# Sheet1.net
KiCad netlist of a schematic drawn in Altium Designer
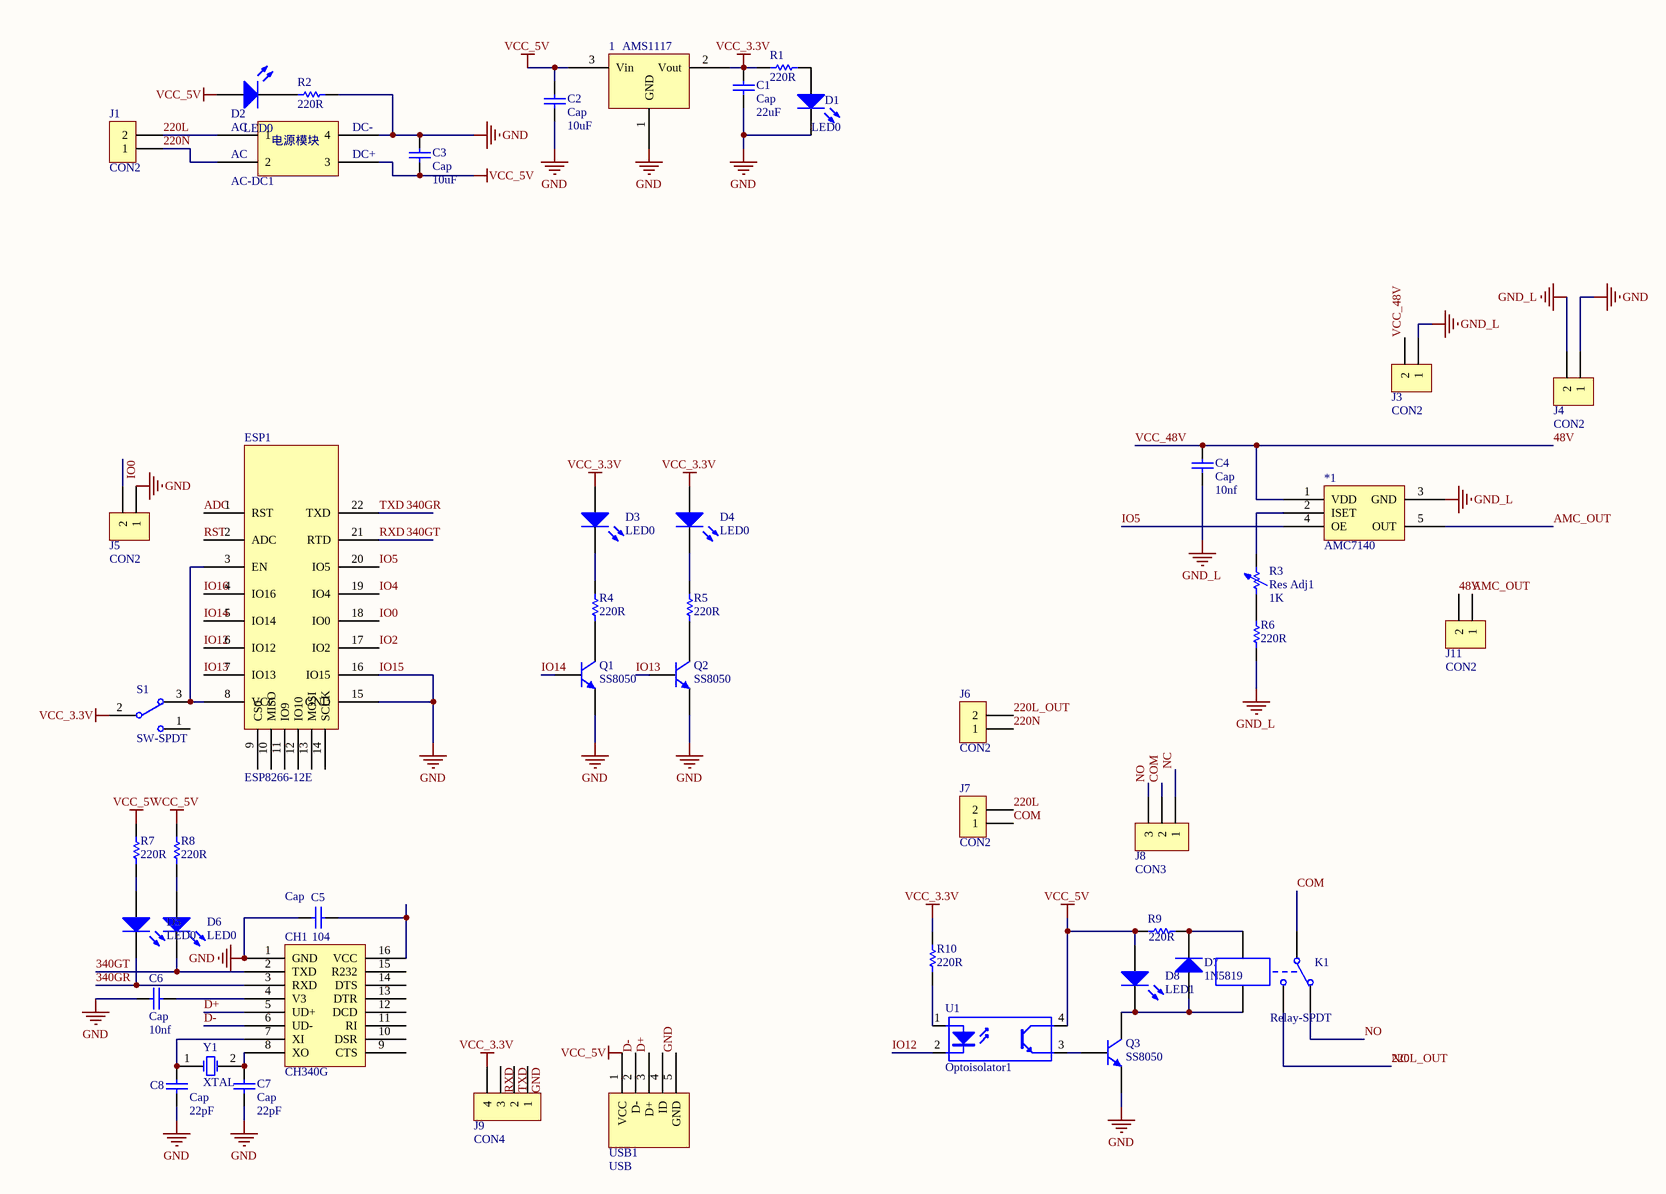
[diagram p0: Sheet1.SchDoc]

(export (version "E")
  (design (tool "Eeschema 10.0.6"))
  (components
    (comp (ref "*1") (value "AMC7140") (footprint "TO-252-5L") (libsource (lib "传感器") (part "AMC7140")))
    (comp (ref "1") (value "AMS1117") (footprint "SOT223") (libsource (lib "开关电路") (part "AMS1117")))
    (comp (ref "AC-DC1") (value "220—5") (footprint "POWER-220_5") (libsource (lib "开关电路") (part "220—5")))
    (comp (ref "C1")
      (value "Cap")
      (footprint "1206")
      (description "Capacitor")
      (fields (field (name "ALTIUM_VALUE") "22uF") (field (name "PUBLISHER") "Altium Limited"))
      (libsource (lib "Miscellaneous Devices0") (part "Cap"))
    )
    (comp (ref "C2")
      (value "Cap")
      (footprint "1206")
      (description "Capacitor")
      (fields (field (name "ALTIUM_VALUE") "10uF") (field (name "PUBLISHER") "Altium Limited"))
      (libsource (lib "Miscellaneous Devices0") (part "Cap"))
    )
    (comp (ref "C3")
      (value "Cap")
      (footprint "CAP-E SMD 8X8")
      (description "Capacitor")
      (fields (field (name "ALTIUM_VALUE") "10uF") (field (name "PUBLISHER") "Altium Limited"))
      (libsource (lib "Miscellaneous Devices0") (part "Cap"))
    )
    (comp (ref "C4")
      (value "Cap")
      (footprint "0805")
      (description "Capacitor")
      (fields (field (name "ALTIUM_VALUE") "10nf") (field (name "PUBLISHER") "Altium Limited"))
      (libsource (lib "Miscellaneous Devices0") (part "Cap"))
    )
    (comp (ref "C5")
      (value "Cap")
      (footprint "0805")
      (description "Capacitor")
      (fields (field (name "ALTIUM_VALUE") "104") (field (name "PUBLISHER") "Altium Limited"))
      (libsource (lib "Miscellaneous Devices0") (part "Cap"))
    )
    (comp (ref "C6")
      (value "Cap")
      (footprint "0805")
      (description "Capacitor")
      (fields (field (name "ALTIUM_VALUE") "10nf") (field (name "PUBLISHER") "Altium Limited"))
      (libsource (lib "Miscellaneous Devices0") (part "Cap"))
    )
    (comp (ref "C7")
      (value "Cap")
      (footprint "0805")
      (description "Capacitor")
      (fields (field (name "ALTIUM_VALUE") "22pF") (field (name "PUBLISHER") "Altium Limited"))
      (libsource (lib "Miscellaneous Devices0") (part "Cap"))
    )
    (comp (ref "C8")
      (value "Cap")
      (footprint "0805")
      (description "Capacitor")
      (fields (field (name "ALTIUM_VALUE") "22pF") (field (name "PUBLISHER") "Altium Limited"))
      (libsource (lib "Miscellaneous Devices0") (part "Cap"))
    )
    (comp (ref "CH1") (value "CH340G") (footprint "SO:SOP16") (libsource (lib "CH340") (part "CH340G")))
    (comp (ref "D1")
      (value "LED0")
      (footprint "ZH常用封装ZH:LED0805")
      (description "Typical INFRARED GaAs LED")
      (fields (field (name "PUBLISHER") "Altium Limited"))
      (libsource (lib "Miscellaneous Devices") (part "LED0"))
    )
    (comp (ref "D2")
      (value "LED0")
      (footprint "ZH常用封装ZH:LED0805")
      (description "Typical INFRARED GaAs LED")
      (fields (field (name "PUBLISHER") "Altium Limited"))
      (libsource (lib "Miscellaneous Devices") (part "LED0"))
    )
    (comp (ref "D3")
      (value "LED0")
      (footprint "ZH常用封装ZH:LED0805")
      (description "Typical INFRARED GaAs LED")
      (fields (field (name "PUBLISHER") "Altium Limited"))
      (libsource (lib "Miscellaneous Devices") (part "LED0"))
    )
    (comp (ref "D4")
      (value "LED0")
      (footprint "ZH常用封装ZH:LED0805")
      (description "Typical INFRARED GaAs LED")
      (fields (field (name "PUBLISHER") "Altium Limited"))
      (libsource (lib "Miscellaneous Devices") (part "LED0"))
    )
    (comp (ref "D5")
      (value "LED0")
      (footprint "ZH常用封装ZH:LED0805")
      (description "Typical INFRARED GaAs LED")
      (fields (field (name "PUBLISHER") "Altium Limited"))
      (libsource (lib "Miscellaneous Devices") (part "LED0"))
    )
    (comp (ref "D6")
      (value "LED0")
      (footprint "ZH常用封装ZH:LED0805")
      (description "Typical INFRARED GaAs LED")
      (fields (field (name "PUBLISHER") "Altium Limited"))
      (libsource (lib "Miscellaneous Devices") (part "LED0"))
    )
    (comp (ref "D7")
      (value "1N5819")
      (footprint "ZH常用封装ZH:DO-214AC/SMA")
      (description "Default Diode")
      (fields (field (name "PUBLISHER") "Altium Limited"))
      (libsource (lib "Miscellaneous Devices") (part "Diode"))
    )
    (comp (ref "D8")
      (value "LED1")
      (footprint "ZH常用封装ZH:LED0805")
      (description "Typical RED GaAs LED")
      (fields (field (name "PUBLISHER") "Altium Limited"))
      (libsource (lib "Miscellaneous Devices") (part "LED1"))
    )
    (comp (ref "ESP1")
      (value "ESP8266-12E")
      (footprint "ZH常用封装ZH:ESP8266")
      (libsource (lib "开关电路") (part "ESP8266"))
    )
    (comp (ref "J1")
      (value "CON2")
      (footprint "miniUSB-b:TML-2-5.08")
      (description "Connector")
      (libsource (lib "") (part "CON2_1"))
    )
    (comp (ref "J3")
      (value "CON2")
      (footprint "miniUSB-b:TML-2-5.08")
      (description "Connector")
      (libsource (lib "插件") (part "CON2"))
    )
    (comp (ref "J4")
      (value "CON2")
      (footprint "HDR1X2")
      (description "Connector")
      (libsource (lib "插件") (part "CON2"))
    )
    (comp (ref "J5")
      (value "CON2")
      (footprint "HDR1X2")
      (description "Connector")
      (libsource (lib "插件") (part "CON2"))
    )
    (comp (ref "J6")
      (value "CON2")
      (footprint "miniUSB-b:TML-2-5.08")
      (description "Connector")
      (libsource (lib "") (part "CON2_1"))
    )
    (comp (ref "J7")
      (value "CON2")
      (footprint "HDR1X2")
      (description "Connector")
      (libsource (lib "") (part "CON2_1"))
    )
    (comp (ref "J8")
      (value "CON3")
      (footprint "TML-3-5.08")
      (description "Connector")
      (libsource (lib "插件") (part "CON3"))
    )
    (comp (ref "J9")
      (value "CON4")
      (footprint "SIP4")
      (description "Connector")
      (libsource (lib "开关电路") (part "CON4"))
    )
    (comp (ref "J11")
      (value "CON2")
      (footprint "miniUSB-b:TML-2-5.08")
      (description "Connector")
      (libsource (lib "插件") (part "CON2"))
    )
    (comp (ref "K1")
      (value "Relay-SPDT")
      (footprint "5V-5")
      (description "Single-Pole Dual-Throw Relay")
      (fields (field (name "PUBLISHER") "Altium Limited"))
      (libsource (lib "Miscellaneous Devices") (part "Relay-SPDT"))
    )
    (comp (ref "Q1")
      (value "SS8050")
      (footprint "SOT-23")
      (description "NPN General Purpose Amplifier")
      (fields (field (name "PUBLISHER") "Altium Limited"))
      (libsource (lib "Miscellaneous Devices") (part "2N3904"))
    )
    (comp (ref "Q2")
      (value "SS8050")
      (footprint "SOT-23")
      (description "NPN General Purpose Amplifier")
      (fields (field (name "PUBLISHER") "Altium Limited"))
      (libsource (lib "Miscellaneous Devices") (part "2N3904"))
    )
    (comp (ref "Q3")
      (value "SS8050")
      (footprint "SOT-23")
      (description "NPN General Purpose Amplifier")
      (fields (field (name "PUBLISHER") "Altium Limited"))
      (libsource (lib "Miscellaneous Devices") (part "2N3904"))
    )
    (comp (ref "R1")
      (value "220R")
      (footprint "贴片:0805")
      (description "Resistor")
      (fields (field (name "Comment") "Res") (field (name "PUBLISHER") "Altium Limited"))
      (libsource (lib "电阻电容") (part "Res"))
    )
    (comp (ref "R2")
      (value "220R")
      (footprint "贴片:0805")
      (description "Resistor")
      (fields (field (name "Comment") "Res") (field (name "PUBLISHER") "Altium Limited"))
      (libsource (lib "电阻电容") (part "Res"))
    )
    (comp (ref "R3")
      (value "Res Adj1")
      (footprint "RES ADJ-3296W")
      (description "Variable Resistor")
      (fields (field (name "ALTIUM_VALUE") "1K") (field (name "PUBLISHER") "Altium Limited"))
      (libsource (lib "Miscellaneous Devices") (part "Res Adj1"))
    )
    (comp (ref "R4")
      (value "220R")
      (footprint "贴片:0805")
      (description "Resistor")
      (fields (field (name "Comment") "Res") (field (name "PUBLISHER") "Altium Limited"))
      (libsource (lib "电阻电容") (part "Res"))
    )
    (comp (ref "R5")
      (value "220R")
      (footprint "贴片:0805")
      (description "Resistor")
      (fields (field (name "Comment") "Res") (field (name "PUBLISHER") "Altium Limited"))
      (libsource (lib "电阻电容") (part "Res"))
    )
    (comp (ref "R6")
      (value "220R")
      (footprint "贴片:0805")
      (description "Resistor")
      (fields (field (name "Comment") "Res") (field (name "PUBLISHER") "Altium Limited"))
      (libsource (lib "电阻电容") (part "Res"))
    )
    (comp (ref "R7")
      (value "220R")
      (footprint "贴片:0805")
      (description "Resistor")
      (fields (field (name "Comment") "Res") (field (name "PUBLISHER") "Altium Limited"))
      (libsource (lib "电阻电容") (part "Res"))
    )
    (comp (ref "R8")
      (value "220R")
      (footprint "贴片:0805")
      (description "Resistor")
      (fields (field (name "Comment") "Res") (field (name "PUBLISHER") "Altium Limited"))
      (libsource (lib "电阻电容") (part "Res"))
    )
    (comp (ref "R9")
      (value "220R")
      (footprint "贴片:0805")
      (description "Resistor")
      (fields (field (name "Comment") "Res") (field (name "PUBLISHER") "Altium Limited"))
      (libsource (lib "电阻电容") (part "Res"))
    )
    (comp (ref "R10")
      (value "220R")
      (footprint "贴片:0805")
      (description "Resistor")
      (fields (field (name "Comment") "Res") (field (name "PUBLISHER") "Altium Limited"))
      (libsource (lib "电阻电容") (part "Res"))
    )
    (comp (ref "S1")
      (value "SW-SPDT")
      (footprint "SS12D00G3")
      (description "SPDT Subminiature Toggle Switch, Right Angle Mounting, Vertical Actuation")
      (fields (field (name "PUBLISHER") "Altium Limited"))
      (libsource (lib "Miscellaneous Devices") (part "SW-SPDT"))
    )
    (comp (ref "U1")
      (value "Optoisolator1")
      (footprint "DIP4")
      (description "4-Pin Phototransistor Optocoupler")
      (fields (field (name "PUBLISHER") "Altium Limited"))
      (libsource (lib "Miscellaneous Devices") (part "Optoisolator1"))
    )
    (comp (ref "USB1")
      (value "USB")
      (footprint "ZH常用封装ZH:USB-MINI")
      (libsource (lib "CH340") (part "miniUSB-b"))
    )
    (comp (ref "Y1")
      (value "XTAL")
      (footprint "XTAL")
      (description "Crystal Oscillator")
      (fields (field (name "PUBLISHER") "Altium Limited"))
      (libsource (lib "Miscellaneous Devices0") (part "XTAL"))
    )
  )
  (nets
    (net (code "1") (name "/48V") (class "Default")
      (node (ref "*1") (pin "1") (pinfunction "VDD_1") (pintype "passive"))
      (node (ref "C4") (pin "1") (pinfunction "1_1") (pintype "passive"))
      (node (ref "J11") (pin "2") (pinfunction "2_2") (pintype "passive"))
      (node (ref "J3") (pin "2") (pinfunction "2_2") (pintype "passive"))
    )
    (net (code "2") (name "/220L") (class "Default")
      (node (ref "AC-DC1") (pin "1") (pinfunction "1_1") (pintype "passive"))
      (node (ref "J1") (pin "2") (pinfunction "2_2") (pintype "passive"))
      (node (ref "J7") (pin "2") (pinfunction "2_2") (pintype "passive"))
    )
    (net (code "3") (name "/220L_OUT") (class "Default")
      (node (ref "J6") (pin "2") (pinfunction "2_2") (pintype "passive"))
      (node (ref "J8") (pin "1") (pinfunction "1_1") (pintype "passive"))
      (node (ref "K1") (pin "3") (pinfunction "3_3") (pintype "passive"))
    )
    (net (code "4") (name "/220N") (class "Default")
      (node (ref "AC-DC1") (pin "2") (pinfunction "2_2") (pintype "passive"))
      (node (ref "J1") (pin "1") (pinfunction "1_1") (pintype "passive"))
      (node (ref "J6") (pin "1") (pinfunction "1_1") (pintype "passive"))
    )
    (net (code "5") (name "/340GR") (class "Default")
      (node (ref "CH1") (pin "3") (pinfunction "RXD_3") (pintype "passive"))
      (node (ref "D5") (pin "2") (pinfunction "K_2") (pintype "passive"))
      (node (ref "ESP1") (pin "22") (pinfunction "TXD_22") (pintype "passive"))
      (node (ref "J9") (pin "2") (pinfunction "2_2") (pintype "passive"))
    )
    (net (code "6") (name "/340GT") (class "Default")
      (node (ref "CH1") (pin "2") (pinfunction "TXD_2") (pintype "passive"))
      (node (ref "D6") (pin "2") (pinfunction "K_2") (pintype "passive"))
      (node (ref "ESP1") (pin "21") (pinfunction "RTD_21") (pintype "passive"))
      (node (ref "J9") (pin "3") (pinfunction "3_3") (pintype "passive"))
    )
    (net (code "7") (name "/ADC") (class "Default")
      (node (ref "ESP1") (pin "1") (pinfunction "RST_1") (pintype "passive"))
    )
    (net (code "8") (name "/AMC_OUT") (class "Default")
      (node (ref "*1") (pin "5") (pinfunction "OUT_5") (pintype "passive"))
      (node (ref "J11") (pin "1") (pinfunction "1_1") (pintype "passive"))
    )
    (net (code "9") (name "/COM") (class "Default")
      (node (ref "J7") (pin "1") (pinfunction "1_1") (pintype "passive"))
      (node (ref "J8") (pin "2") (pinfunction "2_2") (pintype "passive"))
      (node (ref "K1") (pin "1") (pinfunction "1_1") (pintype "passive"))
    )
    (net (code "10") (name "/D+") (class "Default")
      (node (ref "CH1") (pin "5") (pinfunction "UD+_5") (pintype "passive"))
      (node (ref "USB1") (pin "3") (pinfunction "D+_3") (pintype "passive"))
    )
    (net (code "11") (name "/D-") (class "Default")
      (node (ref "CH1") (pin "6") (pinfunction "UD-_6") (pintype "passive"))
      (node (ref "USB1") (pin "2") (pinfunction "D-_2") (pintype "passive"))
    )
    (net (code "12") (name "/IO0") (class "Default")
      (node (ref "ESP1") (pin "18") (pinfunction "IO0_18") (pintype "passive"))
      (node (ref "J5") (pin "2") (pinfunction "2_2") (pintype "passive"))
    )
    (net (code "13") (name "/IO2") (class "Default")
      (node (ref "ESP1") (pin "17") (pinfunction "IO2_17") (pintype "passive"))
    )
    (net (code "14") (name "/IO4") (class "Default")
      (node (ref "ESP1") (pin "19") (pinfunction "IO4_19") (pintype "passive"))
    )
    (net (code "15") (name "/IO5") (class "Default")
      (node (ref "*1") (pin "4") (pinfunction "OE_4") (pintype "passive"))
      (node (ref "ESP1") (pin "20") (pinfunction "IO5_20") (pintype "passive"))
    )
    (net (code "16") (name "/IO12") (class "Default")
      (node (ref "ESP1") (pin "6") (pinfunction "IO12_6") (pintype "passive"))
      (node (ref "U1") (pin "2") (pinfunction "K_2") (pintype "passive"))
    )
    (net (code "17") (name "/IO13") (class "Default")
      (node (ref "ESP1") (pin "7") (pinfunction "IO13_7") (pintype "passive"))
      (node (ref "Q2") (pin "2") (pinfunction "B_2") (pintype "passive"))
    )
    (net (code "18") (name "/IO14") (class "Default")
      (node (ref "ESP1") (pin "5") (pinfunction "IO14_5") (pintype "passive"))
      (node (ref "Q1") (pin "2") (pinfunction "B_2") (pintype "passive"))
    )
    (net (code "19") (name "/IO16") (class "Default")
      (node (ref "ESP1") (pin "4") (pinfunction "IO16_4") (pintype "passive"))
    )
    (net (code "20") (name "/NO") (class "Default")
      (node (ref "J8") (pin "3") (pinfunction "3_3") (pintype "passive"))
      (node (ref "K1") (pin "2") (pinfunction "2_2") (pintype "passive"))
    )
    (net (code "21") (name "/RST") (class "Default")
      (node (ref "ESP1") (pin "2") (pinfunction "ADC_2") (pintype "passive"))
    )
    (net (code "22") (name "GND") (class "Default")
      (node (ref "1") (pin "1") (pinfunction "GND_1") (pintype "passive"))
      (node (ref "AC-DC1") (pin "4") (pinfunction "4_4") (pintype "passive"))
      (node (ref "C1") (pin "2") (pinfunction "2_2") (pintype "passive"))
      (node (ref "C2") (pin "2") (pinfunction "2_2") (pintype "passive"))
      (node (ref "C3") (pin "1") (pinfunction "1_1") (pintype "passive"))
      (node (ref "C5") (pin "2") (pinfunction "2_2") (pintype "passive"))
      (node (ref "C6") (pin "2") (pinfunction "2_2") (pintype "passive"))
      (node (ref "C7") (pin "1") (pinfunction "1_1") (pintype "passive"))
      (node (ref "C8") (pin "1") (pinfunction "1_1") (pintype "passive"))
      (node (ref "CH1") (pin "1") (pinfunction "GND_1") (pintype "passive"))
      (node (ref "D1") (pin "2") (pinfunction "K_2") (pintype "passive"))
      (node (ref "ESP1") (pin "15") (pinfunction "GND_15") (pintype "passive"))
      (node (ref "ESP1") (pin "16") (pinfunction "IO15_16") (pintype "passive"))
      (node (ref "J4") (pin "1") (pinfunction "1_1") (pintype "passive"))
      (node (ref "J5") (pin "1") (pinfunction "1_1") (pintype "passive"))
      (node (ref "J9") (pin "1") (pinfunction "1_1") (pintype "passive"))
      (node (ref "Q1") (pin "1") (pinfunction "E_1") (pintype "passive"))
      (node (ref "Q2") (pin "1") (pinfunction "E_1") (pintype "passive"))
      (node (ref "Q3") (pin "1") (pinfunction "E_1") (pintype "passive"))
      (node (ref "R2") (pin "1") (pinfunction "1_1") (pintype "passive"))
      (node (ref "USB1") (pin "5") (pinfunction "GND_5") (pintype "passive"))
    )
    (net (code "23") (name "GND_L") (class "Default")
      (node (ref "*1") (pin "3") (pinfunction "GND_3") (pintype "passive"))
      (node (ref "C4") (pin "2") (pinfunction "2_2") (pintype "passive"))
      (node (ref "J3") (pin "1") (pinfunction "1_1") (pintype "passive"))
      (node (ref "J4") (pin "2") (pinfunction "2_2") (pintype "passive"))
      (node (ref "R6") (pin "1") (pinfunction "1_1") (pintype "passive"))
    )
    (net (code "24") (name "Net-(*1-ISET)") (class "Default")
      (node (ref "*1") (pin "2") (pinfunction "ISET_2") (pintype "passive"))
      (node (ref "R3") (pin "2") (pinfunction "2_2") (pintype "passive"))
    )
    (net (code "25") (name "Net-(CH1-V3)") (class "Default")
      (node (ref "C6") (pin "1") (pinfunction "1_1") (pintype "passive"))
      (node (ref "CH1") (pin "4") (pinfunction "V3_4") (pintype "passive"))
    )
    (net (code "26") (name "Net-(CH1-VCC)") (class "Default")
      (node (ref "C5") (pin "1") (pinfunction "1_1") (pintype "passive"))
      (node (ref "CH1") (pin "16") (pinfunction "VCC_16") (pintype "passive"))
    )
    (net (code "27") (name "Net-(CH1-XI)") (class "Default")
      (node (ref "C8") (pin "2") (pinfunction "2_2") (pintype "passive"))
      (node (ref "CH1") (pin "7") (pinfunction "XI_7") (pintype "passive"))
      (node (ref "Y1") (pin "1") (pinfunction "OSC1_1") (pintype "passive"))
    )
    (net (code "28") (name "Net-(CH1-XO)") (class "Default")
      (node (ref "C7") (pin "2") (pinfunction "2_2") (pintype "passive"))
      (node (ref "CH1") (pin "8") (pinfunction "XO_8") (pintype "passive"))
      (node (ref "Y1") (pin "2") (pinfunction "OSC2_2") (pintype "passive"))
    )
    (net (code "29") (name "Net-(D1-A)") (class "Default")
      (node (ref "D1") (pin "1") (pinfunction "A_1") (pintype "passive"))
      (node (ref "R1") (pin "1") (pinfunction "1_1") (pintype "passive"))
    )
    (net (code "30") (name "Net-(D2-K)") (class "Default")
      (node (ref "D2") (pin "2") (pinfunction "K_2") (pintype "passive"))
      (node (ref "R2") (pin "2") (pinfunction "2_2") (pintype "passive"))
    )
    (net (code "31") (name "Net-(D3-K)") (class "Default")
      (node (ref "D3") (pin "2") (pinfunction "K_2") (pintype "passive"))
      (node (ref "R4") (pin "2") (pinfunction "2_2") (pintype "passive"))
    )
    (net (code "32") (name "Net-(D4-K)") (class "Default")
      (node (ref "D4") (pin "2") (pinfunction "K_2") (pintype "passive"))
      (node (ref "R5") (pin "2") (pinfunction "2_2") (pintype "passive"))
    )
    (net (code "33") (name "Net-(D5-A)") (class "Default")
      (node (ref "D5") (pin "1") (pinfunction "A_1") (pintype "passive"))
      (node (ref "R7") (pin "1") (pinfunction "1_1") (pintype "passive"))
    )
    (net (code "34") (name "Net-(D6-A)") (class "Default")
      (node (ref "D6") (pin "1") (pinfunction "A_1") (pintype "passive"))
      (node (ref "R8") (pin "1") (pinfunction "1_1") (pintype "passive"))
    )
    (net (code "35") (name "Net-(D7-A)") (class "Default")
      (node (ref "D7") (pin "1") (pinfunction "A_1") (pintype "passive"))
      (node (ref "D8") (pin "2") (pinfunction "K_2") (pintype "passive"))
      (node (ref "K1") (pin "5") (pinfunction "5_5") (pintype "passive"))
      (node (ref "Q3") (pin "3") (pinfunction "C_3") (pintype "passive"))
    )
    (net (code "36") (name "Net-(D7-K)") (class "Default")
      (node (ref "D7") (pin "2") (pinfunction "K_2") (pintype "passive"))
      (node (ref "K1") (pin "4") (pinfunction "4_4") (pintype "passive"))
      (node (ref "R9") (pin "2") (pinfunction "2_2") (pintype "passive"))
    )
    (net (code "37") (name "Net-(ESP1-EN)") (class "Default")
      (node (ref "ESP1") (pin "3") (pinfunction "EN_3") (pintype "passive"))
      (node (ref "ESP1") (pin "8") (pinfunction "VCC_8") (pintype "passive"))
      (node (ref "S1") (pin "3") (pinfunction "3_3") (pintype "passive"))
    )
    (net (code "38") (name "Net-(Q1-C)") (class "Default")
      (node (ref "Q1") (pin "3") (pinfunction "C_3") (pintype "passive"))
      (node (ref "R4") (pin "1") (pinfunction "1_1") (pintype "passive"))
    )
    (net (code "39") (name "Net-(Q2-C)") (class "Default")
      (node (ref "Q2") (pin "3") (pinfunction "C_3") (pintype "passive"))
      (node (ref "R5") (pin "1") (pinfunction "1_1") (pintype "passive"))
    )
    (net (code "40") (name "Net-(Q3-B)") (class "Default")
      (node (ref "Q3") (pin "2") (pinfunction "B_2") (pintype "passive"))
      (node (ref "U1") (pin "3") (pinfunction "E_3") (pintype "passive"))
    )
    (net (code "41") (name "Net-(R3-Pad1)") (class "Default")
      (node (ref "R3") (pin "1") (pinfunction "1_1") (pintype "passive"))
      (node (ref "R6") (pin "2") (pinfunction "2_2") (pintype "passive"))
    )
    (net (code "42") (name "Net-(U1-A)") (class "Default")
      (node (ref "R10") (pin "1") (pinfunction "1_1") (pintype "passive"))
      (node (ref "U1") (pin "1") (pinfunction "A_1") (pintype "passive"))
    )
    (net (code "43") (name "VCC_3.3V") (class "Default")
      (node (ref "1") (pin "2") (pinfunction "Vout_2") (pintype "passive"))
      (node (ref "C1") (pin "1") (pinfunction "1_1") (pintype "passive"))
      (node (ref "D3") (pin "1") (pinfunction "A_1") (pintype "passive"))
      (node (ref "D4") (pin "1") (pinfunction "A_1") (pintype "passive"))
      (node (ref "J9") (pin "4") (pinfunction "4_4") (pintype "passive"))
      (node (ref "R1") (pin "2") (pinfunction "2_2") (pintype "passive"))
      (node (ref "R10") (pin "2") (pinfunction "2_2") (pintype "passive"))
      (node (ref "S1") (pin "2") (pinfunction "2_2") (pintype "passive"))
    )
    (net (code "44") (name "VCC_5V") (class "Default")
      (node (ref "1") (pin "3") (pinfunction "Vin_3") (pintype "passive"))
      (node (ref "AC-DC1") (pin "3") (pinfunction "3_3") (pintype "passive"))
      (node (ref "C2") (pin "1") (pinfunction "1_1") (pintype "passive"))
      (node (ref "C3") (pin "2") (pinfunction "2_2") (pintype "passive"))
      (node (ref "D2") (pin "1") (pinfunction "A_1") (pintype "passive"))
      (node (ref "D8") (pin "1") (pinfunction "A_1") (pintype "passive"))
      (node (ref "R7") (pin "2") (pinfunction "2_2") (pintype "passive"))
      (node (ref "R8") (pin "2") (pinfunction "2_2") (pintype "passive"))
      (node (ref "R9") (pin "1") (pinfunction "1_1") (pintype "passive"))
      (node (ref "U1") (pin "4") (pinfunction "C_4") (pintype "passive"))
      (node (ref "USB1") (pin "1") (pinfunction "VCC_1") (pintype "passive"))
    )
    (net (code "45") (name "unconnected-(CH1-CTS-Pad9)") (class "Default")
      (node (ref "CH1") (pin "9") (pinfunction "CTS_9") (pintype "passive"))
    )
    (net (code "46") (name "unconnected-(CH1-DCD-Pad12)") (class "Default")
      (node (ref "CH1") (pin "12") (pinfunction "DCD_12") (pintype "passive"))
    )
    (net (code "47") (name "unconnected-(CH1-DSR-Pad10)") (class "Default")
      (node (ref "CH1") (pin "10") (pinfunction "DSR_10") (pintype "passive"))
    )
    (net (code "48") (name "unconnected-(CH1-DTR-Pad13)") (class "Default")
      (node (ref "CH1") (pin "13") (pinfunction "DTR_13") (pintype "passive"))
    )
    (net (code "49") (name "unconnected-(CH1-DTS-Pad14)") (class "Default")
      (node (ref "CH1") (pin "14") (pinfunction "DTS_14") (pintype "passive"))
    )
    (net (code "50") (name "unconnected-(CH1-R232-Pad15)") (class "Default")
      (node (ref "CH1") (pin "15") (pinfunction "R232_15") (pintype "passive"))
    )
    (net (code "51") (name "unconnected-(CH1-RI-Pad11)") (class "Default")
      (node (ref "CH1") (pin "11") (pinfunction "RI_11") (pintype "passive"))
    )
    (net (code "52") (name "unconnected-(ESP1-CS0-Pad9)") (class "Default")
      (node (ref "ESP1") (pin "9") (pinfunction "CS0_9") (pintype "passive"))
    )
    (net (code "53") (name "unconnected-(ESP1-IO9-Pad11)") (class "Default")
      (node (ref "ESP1") (pin "11") (pinfunction "IO9_11") (pintype "passive"))
    )
    (net (code "54") (name "unconnected-(ESP1-IO10-Pad12)") (class "Default")
      (node (ref "ESP1") (pin "12") (pinfunction "IO10_12") (pintype "passive"))
    )
    (net (code "55") (name "unconnected-(ESP1-MISO-Pad10)") (class "Default")
      (node (ref "ESP1") (pin "10") (pinfunction "MISO_10") (pintype "passive"))
    )
    (net (code "56") (name "unconnected-(ESP1-MOSI-Pad13)") (class "Default")
      (node (ref "ESP1") (pin "13") (pinfunction "MOSI_13") (pintype "passive"))
    )
    (net (code "57") (name "unconnected-(ESP1-SCLK-Pad14)") (class "Default")
      (node (ref "ESP1") (pin "14") (pinfunction "SCLK_14") (pintype "passive"))
    )
    (net (code "58") (name "unconnected-(S1-Pad1)") (class "Default")
      (node (ref "S1") (pin "1") (pinfunction "1_1") (pintype "passive"))
    )
    (net (code "59") (name "unconnected-(USB1-ID-Pad4)") (class "Default")
      (node (ref "USB1") (pin "4") (pinfunction "ID_4") (pintype "passive"))
    )
  )
)
